# LEDDriver_v_1.net
KiCad netlist of a schematic drawn in EAGLE
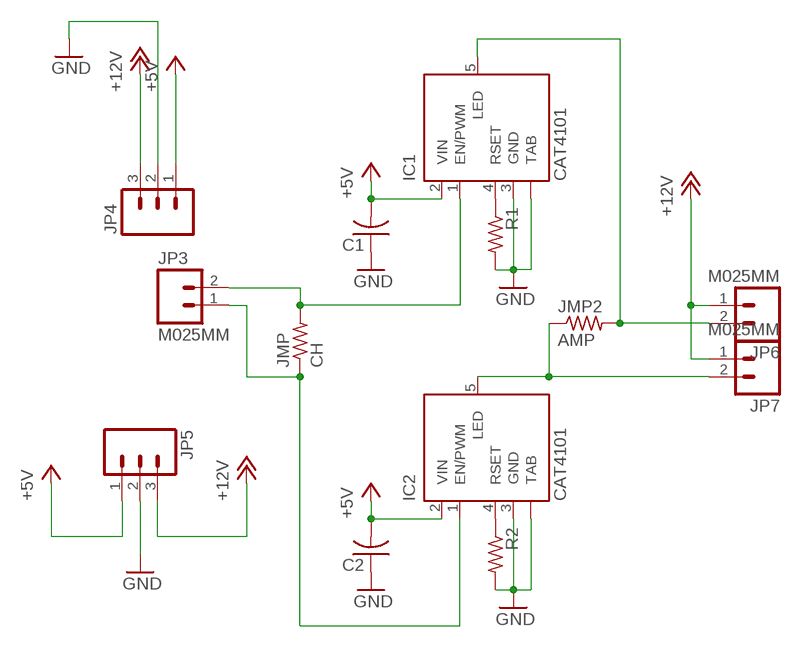
[diagram p0: schematic, sheet 1]

(export (version "E")
  (design (tool "Eeschema 10.0.6"))
  (components
    (comp (ref "C1")
      (value "C-USC1206")
      (footprint "eagle-import:C1206")
      (libsource (lib "eagle-import") (part "C-USC1206"))
    )
    (comp (ref "C2")
      (value "C-USC1206")
      (footprint "eagle-import:C1206")
      (libsource (lib "eagle-import") (part "C-USC1206"))
    )
    (comp (ref "IC1")
      (value "CAT4101")
      (footprint "eagle-import:TO263_5")
      (fields (field (name "MPN") "CAT4101TV-T75"))
      (libsource (lib "eagle-import") (part "CAT4101"))
    )
    (comp (ref "IC2")
      (value "CAT4101")
      (footprint "eagle-import:TO263_5")
      (fields (field (name "MPN") "CAT4101TV-T75"))
      (libsource (lib "eagle-import") (part "CAT4101"))
    )
    (comp (ref "JMP")
      (value "CH")
      (footprint "eagle-import:R1206")
      (libsource (lib "eagle-import") (part "R-US_R1206"))
    )
    (comp (ref "JMP2")
      (value "AMP")
      (footprint "eagle-import:R1206")
      (libsource (lib "eagle-import") (part "R-US_R1206"))
    )
    (comp (ref "JP3")
      (value "M025MM")
      (footprint "eagle-import:SCREWTERMINAL-5MM-2")
      (libsource (lib "eagle-import") (part "M025MM"))
    )
    (comp (ref "JP4")
      (value "M03-SCREW-5MM")
      (footprint "eagle-import:SCREWTERMINAL-5MM-3")
      (libsource (lib "eagle-import") (part "M03-SCREW-5MM"))
    )
    (comp (ref "JP5")
      (value "M03-SCREW-5MM")
      (footprint "eagle-import:SCREWTERMINAL-5MM-3")
      (libsource (lib "eagle-import") (part "M03-SCREW-5MM"))
    )
    (comp (ref "JP6")
      (value "M025MM")
      (footprint "eagle-import:SCREWTERMINAL-5MM-2")
      (libsource (lib "eagle-import") (part "M025MM"))
    )
    (comp (ref "JP7")
      (value "M025MM")
      (footprint "eagle-import:SCREWTERMINAL-5MM-2")
      (libsource (lib "eagle-import") (part "M025MM"))
    )
    (comp (ref "R1")
      (value "R-US_R1206")
      (footprint "eagle-import:R1206")
      (libsource (lib "eagle-import") (part "R-US_R1206"))
    )
    (comp (ref "R2")
      (value "R-US_R1206")
      (footprint "eagle-import:R1206")
      (libsource (lib "eagle-import") (part "R-US_R1206"))
    )
  )
  (nets
    (net (code "1") (name "+5V") (class "Default")
      (node (ref "C1") (pin "2") (pinfunction "2_2") (pintype "passive"))
      (node (ref "C2") (pin "2") (pinfunction "2_2") (pintype "passive"))
      (node (ref "IC1") (pin "2") (pinfunction "VIN_2") (pintype "input"))
      (node (ref "IC2") (pin "2") (pinfunction "VIN_2") (pintype "input"))
      (node (ref "JP4") (pin "1") (pinfunction "1_1") (pintype "passive"))
      (node (ref "JP5") (pin "1") (pinfunction "1_1") (pintype "passive"))
    )
    (net (code "2") (name "+12V") (class "Default")
      (node (ref "JP4") (pin "3") (pinfunction "3_3") (pintype "passive"))
      (node (ref "JP5") (pin "3") (pinfunction "3_3") (pintype "passive"))
      (node (ref "JP6") (pin "1") (pinfunction "1_1") (pintype "passive"))
      (node (ref "JP7") (pin "1") (pinfunction "1_1") (pintype "passive"))
    )
    (net (code "3") (name "GND") (class "Default")
      (node (ref "C1") (pin "1") (pinfunction "1_1") (pintype "passive"))
      (node (ref "C2") (pin "1") (pinfunction "1_1") (pintype "passive"))
      (node (ref "IC1") (pin "3") (pinfunction "GND_3") (pintype "power_in"))
      (node (ref "IC1") (pin "TAB") (pinfunction "TAB_TAB") (pintype "passive"))
      (node (ref "IC2") (pin "3") (pinfunction "GND_3") (pintype "power_in"))
      (node (ref "IC2") (pin "TAB") (pinfunction "TAB_TAB") (pintype "passive"))
      (node (ref "JP4") (pin "2") (pinfunction "2_2") (pintype "passive"))
      (node (ref "JP5") (pin "2") (pinfunction "2_2") (pintype "passive"))
      (node (ref "R1") (pin "2") (pinfunction "2_2") (pintype "passive"))
      (node (ref "R2") (pin "2") (pinfunction "2_2") (pintype "passive"))
    )
    (net (code "4") (name "Net-(IC1-EN{slash}PWM)") (class "Default")
      (node (ref "IC1") (pin "1") (pinfunction "EN/PWM_1") (pintype "input"))
      (node (ref "JMP") (pin "2") (pinfunction "2_2") (pintype "passive"))
      (node (ref "JP3") (pin "2") (pinfunction "2_2") (pintype "passive"))
    )
    (net (code "5") (name "Net-(IC1-LED)") (class "Default")
      (node (ref "IC1") (pin "5") (pinfunction "LED_5") (pintype "power_in"))
      (node (ref "JMP2") (pin "2") (pinfunction "2_2") (pintype "passive"))
      (node (ref "JP6") (pin "2") (pinfunction "2_2") (pintype "passive"))
    )
    (net (code "6") (name "Net-(IC1-RSET)") (class "Default")
      (node (ref "IC1") (pin "4") (pinfunction "RSET_4") (pintype "input"))
      (node (ref "R1") (pin "1") (pinfunction "1_1") (pintype "passive"))
    )
    (net (code "7") (name "Net-(IC2-EN{slash}PWM)") (class "Default")
      (node (ref "IC2") (pin "1") (pinfunction "EN/PWM_1") (pintype "input"))
      (node (ref "JMP") (pin "1") (pinfunction "1_1") (pintype "passive"))
      (node (ref "JP3") (pin "1") (pinfunction "1_1") (pintype "passive"))
    )
    (net (code "8") (name "Net-(IC2-LED)") (class "Default")
      (node (ref "IC2") (pin "5") (pinfunction "LED_5") (pintype "power_in"))
      (node (ref "JMP2") (pin "1") (pinfunction "1_1") (pintype "passive"))
      (node (ref "JP7") (pin "2") (pinfunction "2_2") (pintype "passive"))
    )
    (net (code "9") (name "Net-(IC2-RSET)") (class "Default")
      (node (ref "IC2") (pin "4") (pinfunction "RSET_4") (pintype "input"))
      (node (ref "R2") (pin "1") (pinfunction "1_1") (pintype "passive"))
    )
  )
)
